# OPEnS-RTC-1_1.net
KiCad netlist of a schematic drawn in EAGLE
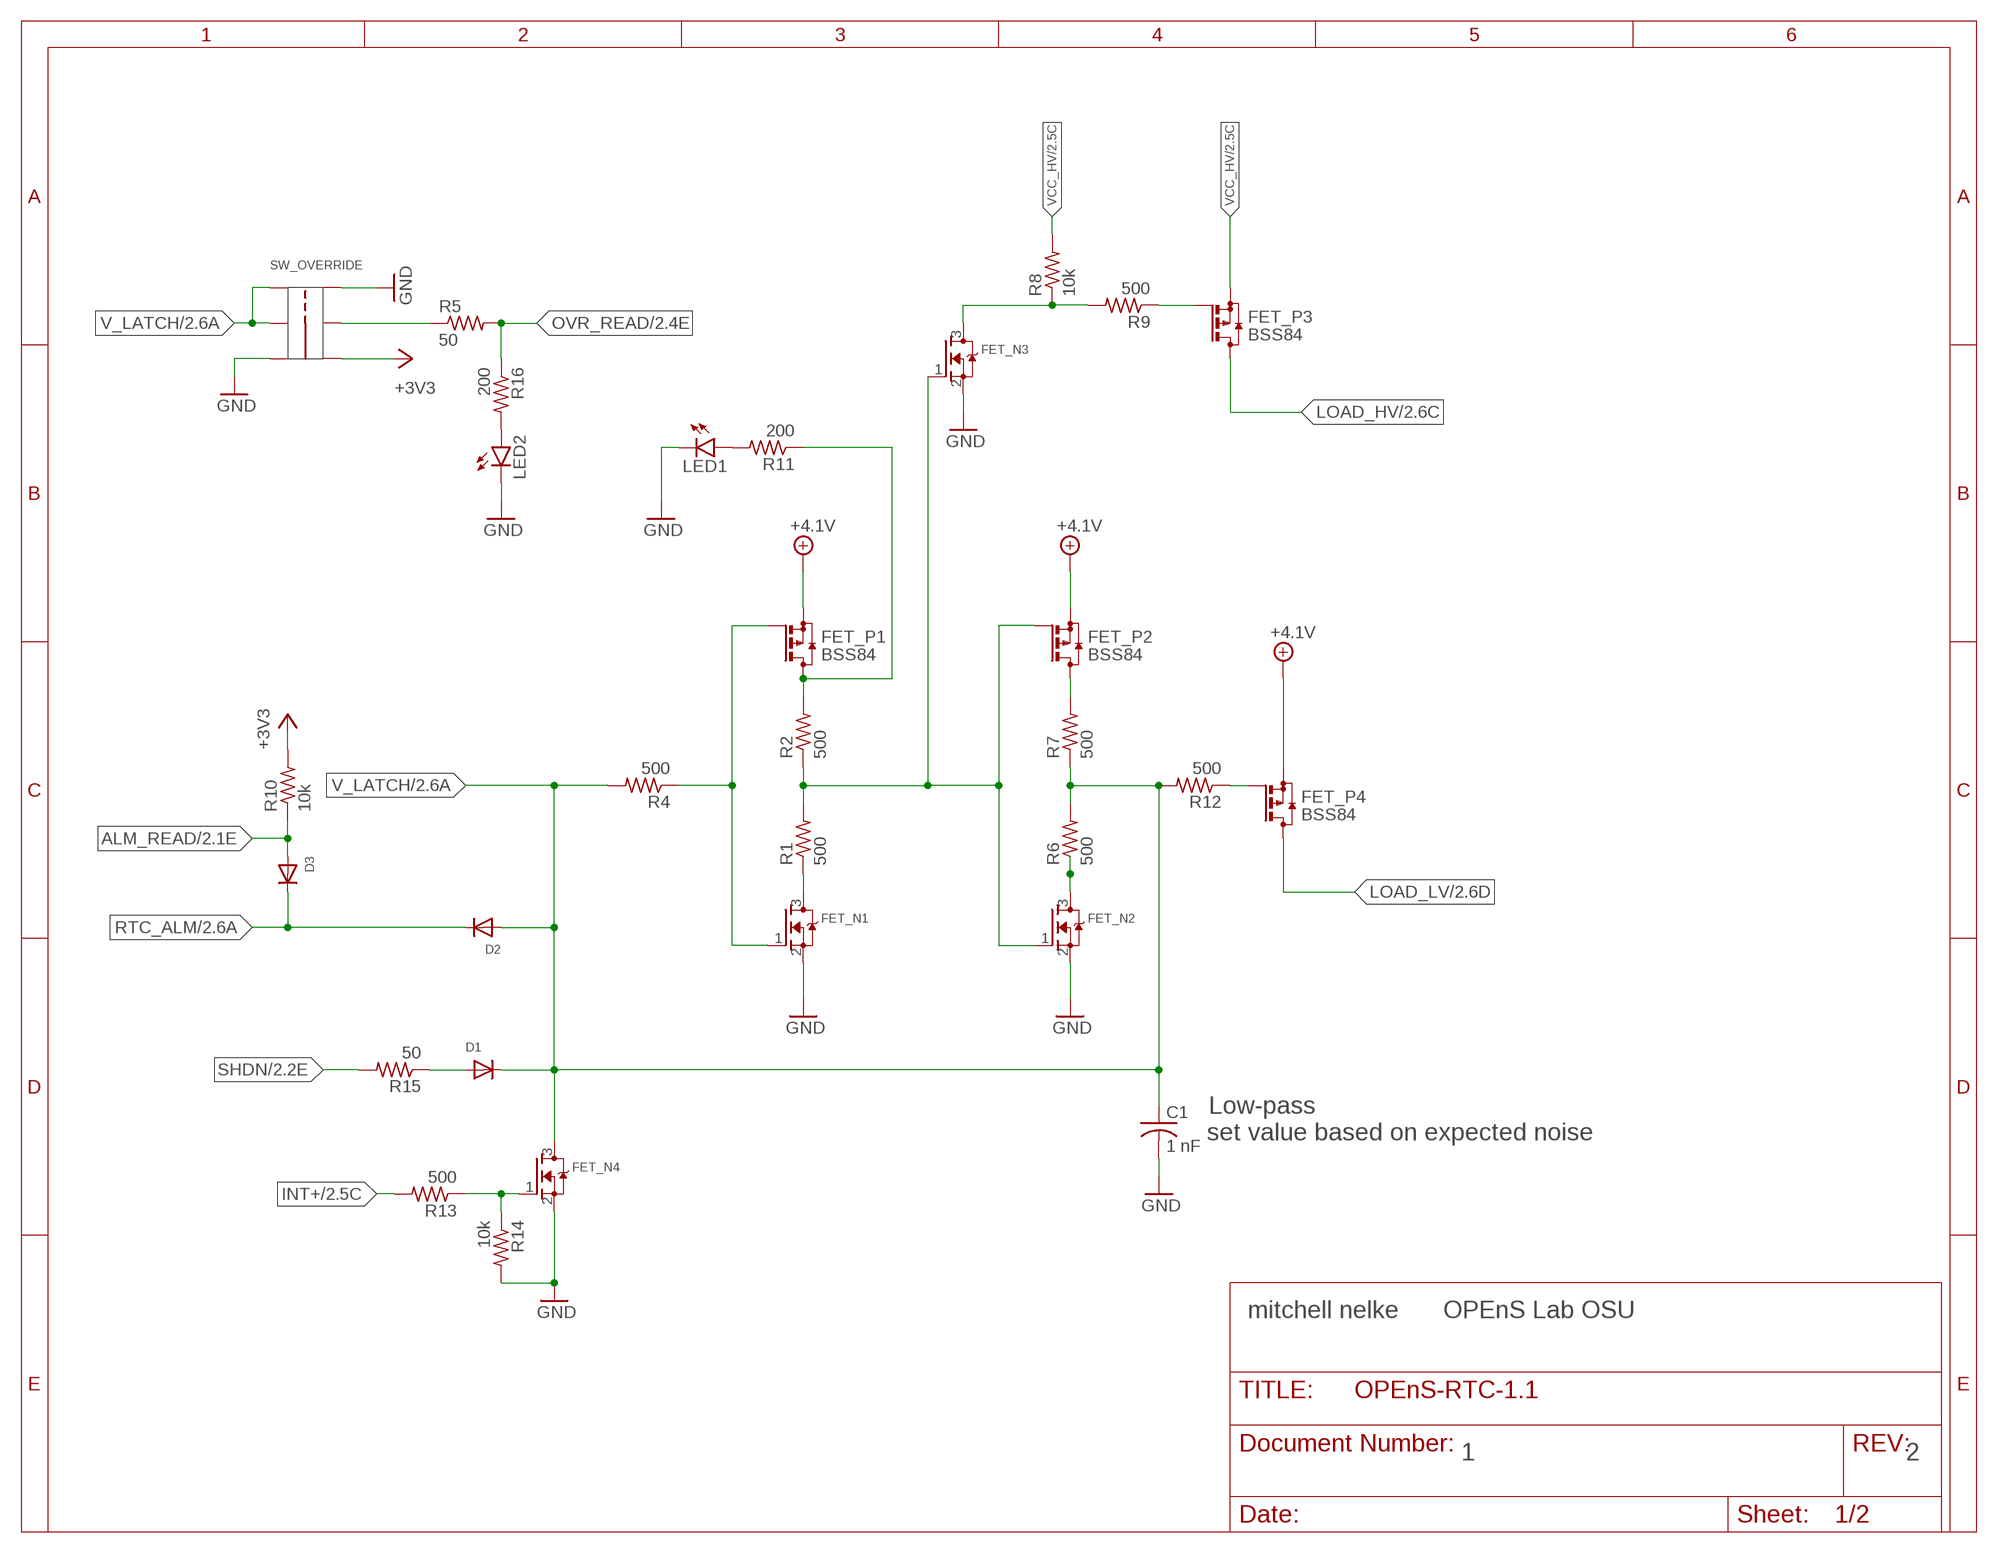
[diagram p0: schematic, sheet 1]
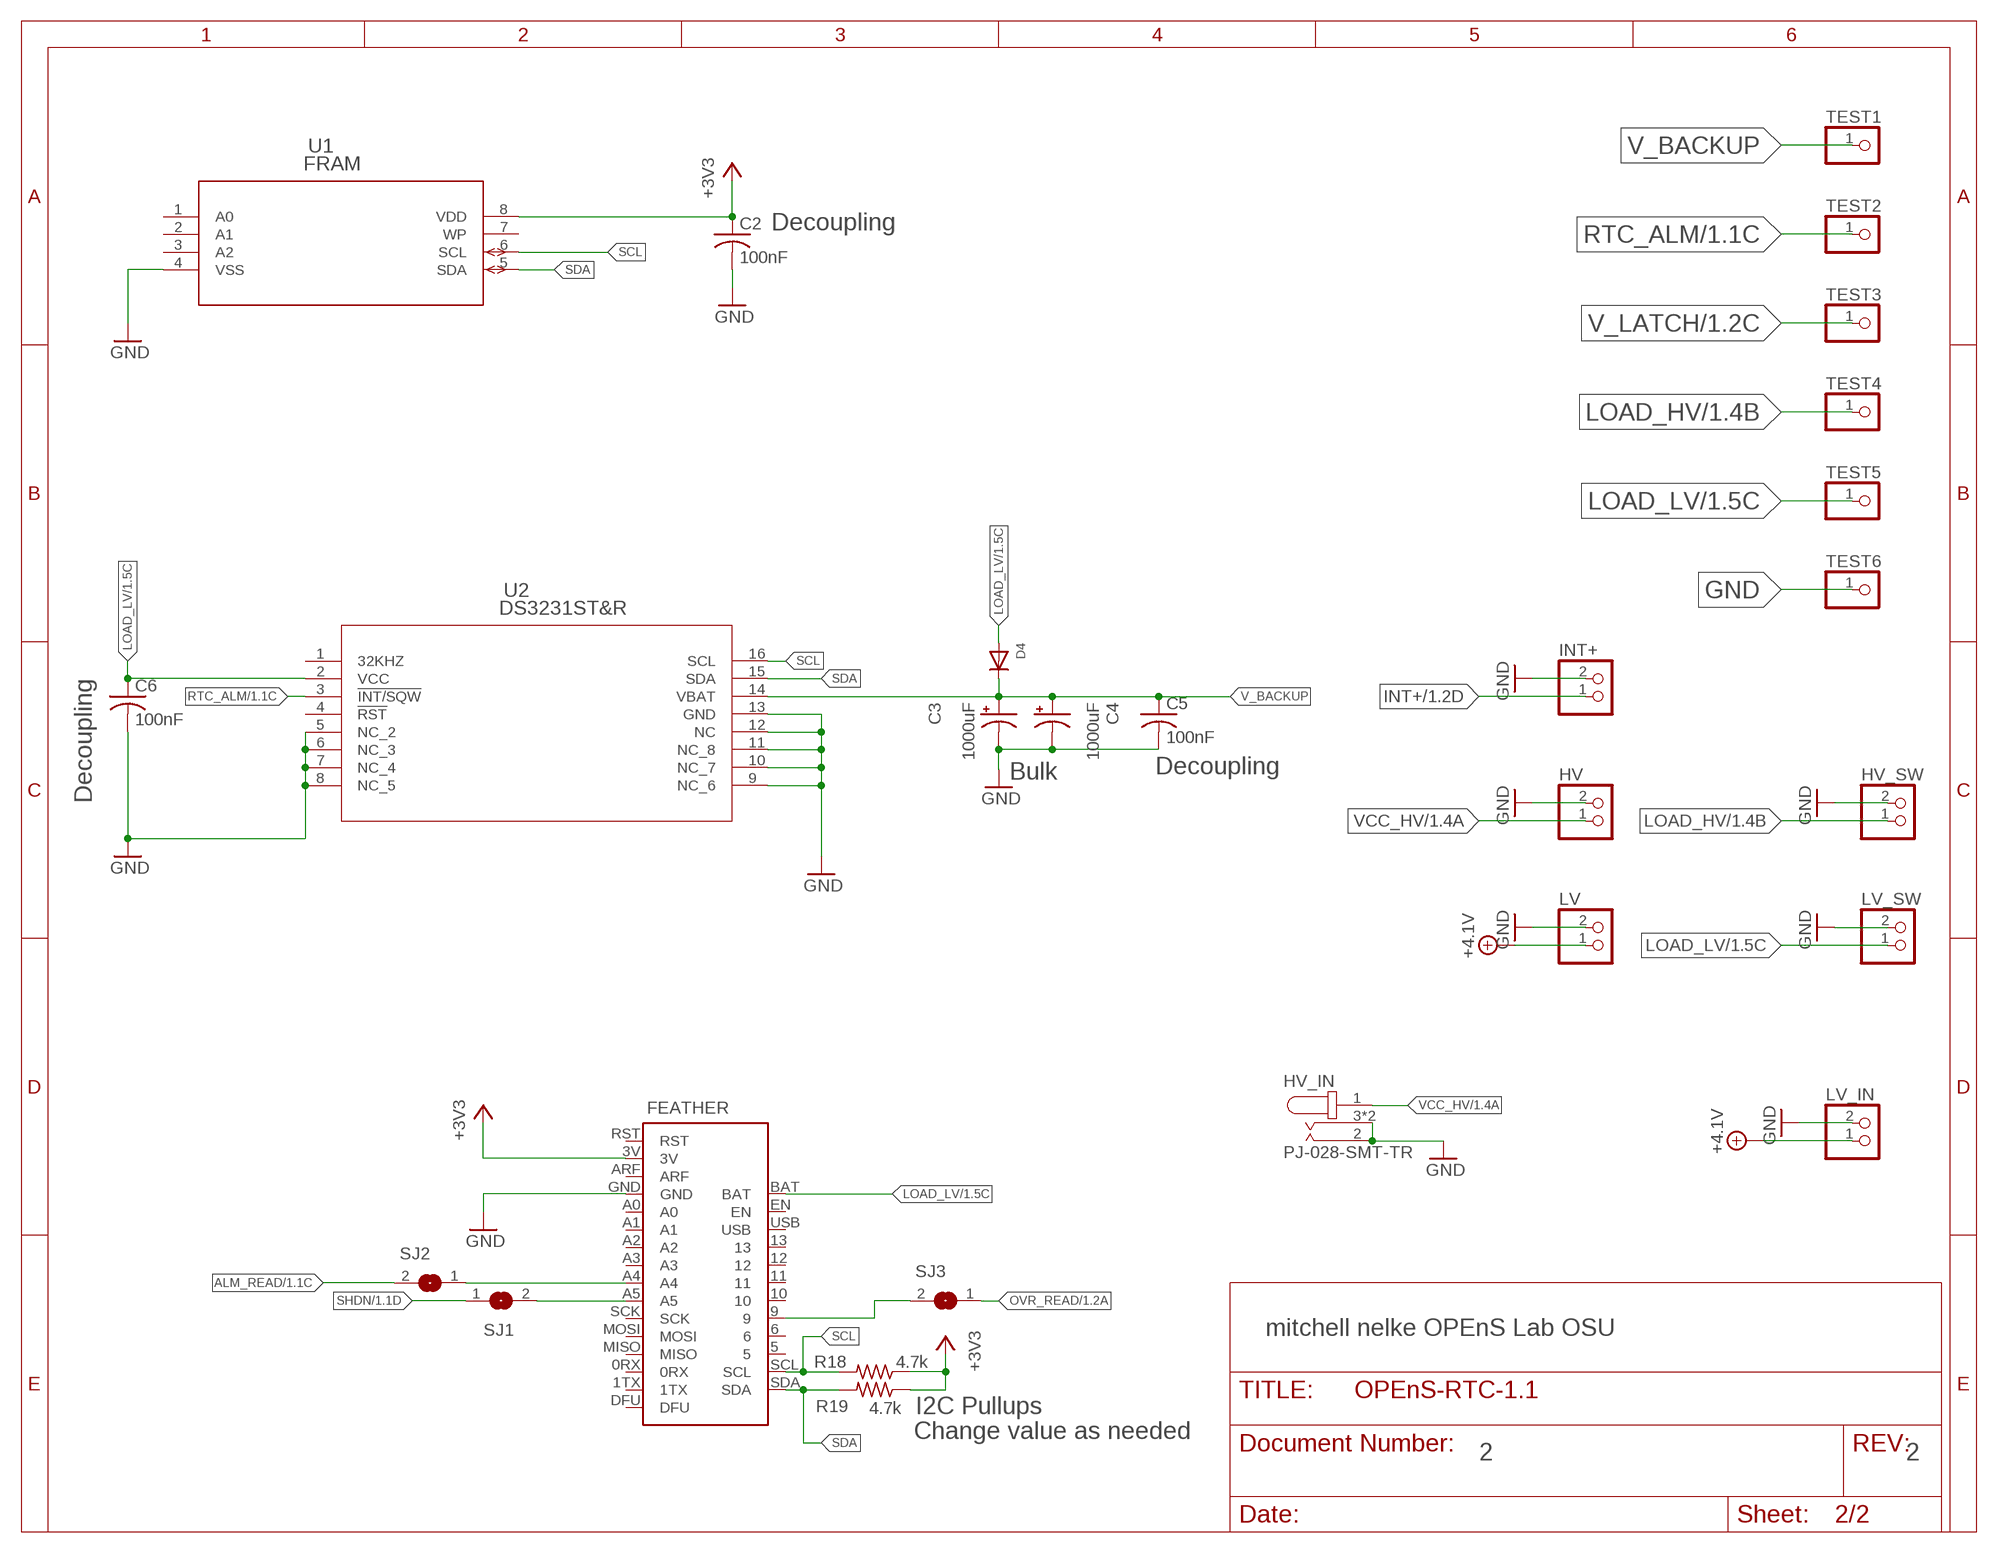
[diagram p1: schematic, sheet 2]

(export (version "E")
  (design (tool "Eeschema 10.0.6"))
  (components
    (comp (ref "C1")
      (value "1 nF")
      (footprint "eagle-import:C0805")
      (libsource (lib "eagle-import") (part "rcl_334_C-USC0805"))
    )
    (comp (ref "D1")
      (value "DIODESOD-123")
      (footprint "eagle-import:SOD-123")
      (libsource (lib "eagle-import") (part "DIODESOD-123"))
    )
    (comp (ref "D2")
      (value "DIODESOD-123")
      (footprint "eagle-import:SOD-123")
      (libsource (lib "eagle-import") (part "DIODESOD-123"))
    )
    (comp (ref "D3")
      (value "DIODESOD-123")
      (footprint "eagle-import:SOD-123")
      (libsource (lib "eagle-import") (part "DIODESOD-123"))
    )
    (comp (ref "FET_N1")
      (value "MOSFET-NREFLOW")
      (footprint "eagle-import:SOT23")
      (libsource (lib "eagle-import") (part "MOSFET-NREFLOW"))
    )
    (comp (ref "FET_N2")
      (value "MOSFET-NREFLOW")
      (footprint "eagle-import:SOT23")
      (libsource (lib "eagle-import") (part "MOSFET-NREFLOW"))
    )
    (comp (ref "FET_N3")
      (value "MOSFET-NREFLOW")
      (footprint "eagle-import:SOT23")
      (libsource (lib "eagle-import") (part "MOSFET-NREFLOW"))
    )
    (comp (ref "FET_N4")
      (value "MOSFET-NREFLOW")
      (footprint "eagle-import:SOT23")
      (libsource (lib "eagle-import") (part "MOSFET-NREFLOW"))
    )
    (comp (ref "FET_P1")
      (value "BSS84")
      (footprint "eagle-import:SOT23")
      (libsource (lib "eagle-import") (part "BSS84"))
    )
    (comp (ref "FET_P2")
      (value "BSS84")
      (footprint "eagle-import:SOT23")
      (libsource (lib "eagle-import") (part "BSS84"))
    )
    (comp (ref "FET_P3")
      (value "BSS84")
      (footprint "eagle-import:SOT23")
      (libsource (lib "eagle-import") (part "BSS84"))
    )
    (comp (ref "FET_P4")
      (value "BSS84")
      (footprint "eagle-import:SOT23")
      (libsource (lib "eagle-import") (part "BSS84"))
    )
    (comp (ref "LED1")
      (value "LEDSMT1206")
      (footprint "eagle-import:1206")
      (libsource (lib "eagle-import") (part "LEDSMT1206"))
    )
    (comp (ref "LED2")
      (value "LEDSMT1206")
      (footprint "eagle-import:1206")
      (libsource (lib "eagle-import") (part "LEDSMT1206"))
    )
    (comp (ref "R1")
      (value "500")
      (footprint "eagle-import:R0805")
      (libsource (lib "eagle-import") (part "rcl_334_R-US_R0805"))
    )
    (comp (ref "R2")
      (value "500")
      (footprint "eagle-import:R0805")
      (libsource (lib "eagle-import") (part "rcl_334_R-US_R0805"))
    )
    (comp (ref "R4")
      (value "500")
      (footprint "eagle-import:R0805")
      (libsource (lib "eagle-import") (part "rcl_334_R-US_R0805"))
    )
    (comp (ref "R5")
      (value "50")
      (footprint "eagle-import:R0805")
      (libsource (lib "eagle-import") (part "rcl_334_R-US_R0805"))
    )
    (comp (ref "R6")
      (value "500")
      (footprint "eagle-import:R0805")
      (libsource (lib "eagle-import") (part "rcl_334_R-US_R0805"))
    )
    (comp (ref "R7")
      (value "500")
      (footprint "eagle-import:R0805")
      (libsource (lib "eagle-import") (part "rcl_334_R-US_R0805"))
    )
    (comp (ref "R8")
      (value "10k")
      (footprint "eagle-import:R0805")
      (libsource (lib "eagle-import") (part "rcl_334_R-US_R0805"))
    )
    (comp (ref "R9")
      (value "500")
      (footprint "eagle-import:R0805")
      (libsource (lib "eagle-import") (part "rcl_334_R-US_R0805"))
    )
    (comp (ref "R10")
      (value "10k")
      (footprint "eagle-import:R0805")
      (libsource (lib "eagle-import") (part "rcl_334_R-US_R0805"))
    )
    (comp (ref "R11")
      (value "200")
      (footprint "eagle-import:R0805")
      (libsource (lib "eagle-import") (part "rcl_334_R-US_R0805"))
    )
    (comp (ref "R12")
      (value "500")
      (footprint "eagle-import:R0805")
      (libsource (lib "eagle-import") (part "rcl_334_R-US_R0805"))
    )
    (comp (ref "R13")
      (value "500")
      (footprint "eagle-import:R0805")
      (libsource (lib "eagle-import") (part "rcl_334_R-US_R0805"))
    )
    (comp (ref "R14")
      (value "10k")
      (footprint "eagle-import:R0805")
      (libsource (lib "eagle-import") (part "rcl_334_R-US_R0805"))
    )
    (comp (ref "R15")
      (value "50")
      (footprint "eagle-import:R0805")
      (libsource (lib "eagle-import") (part "rcl_334_R-US_R0805"))
    )
    (comp (ref "R16")
      (value "200")
      (footprint "eagle-import:R0805")
      (libsource (lib "eagle-import") (part "rcl_334_R-US_R0805"))
    )
    (comp (ref "SW_OVERRIDE")
      (value "JS202011JCQN")
      (footprint "eagle-import:VERTICAL_MNT_SMT-J")
      (libsource (lib "eagle-import") (part "JS202011JCQN"))
    )
    (comp (ref "C2")
      (value "100nF")
      (footprint "eagle-import:C0805")
      (libsource (lib "eagle-import") (part "C-USC0805"))
    )
    (comp (ref "C3")
      (value "1000uF")
      (footprint "eagle-import:E3,5-8")
      (libsource (lib "eagle-import") (part "CPOL-USE3.5-8"))
    )
    (comp (ref "C4")
      (value "1000uF")
      (footprint "eagle-import:E3,5-8")
      (libsource (lib "eagle-import") (part "CPOL-USE3.5-8"))
    )
    (comp (ref "C5")
      (value "100nF")
      (footprint "eagle-import:C0805")
      (libsource (lib "eagle-import") (part "C-USC0805"))
    )
    (comp (ref "C6")
      (value "100nF")
      (footprint "eagle-import:C0805")
      (libsource (lib "eagle-import") (part "C-USC0805"))
    )
    (comp (ref "D4")
      (value "DIODESOD-123")
      (footprint "eagle-import:SOD-123")
      (libsource (lib "eagle-import") (part "DIODESOD-123"))
    )
    (comp (ref "FEATHER")
      (value "BLUEFRUIT_M0")
      (footprint "eagle-import:BLUEFRUIT_MO")
      (libsource (lib "eagle-import") (part "BLUEFRUIT_M0"))
    )
    (comp (ref "HV")
      (value "JST_2PIN-SMT")
      (footprint "eagle-import:JST-PH-2-SMT")
      (libsource (lib "eagle-import") (part "JST_2PIN-SMT"))
    )
    (comp (ref "HV_IN")
      (value "PJ-028-SMT-TR")
      (footprint "eagle-import:CUI_PJ-028-SMT-TR")
      (fields (field (name "DIGI-KEY_PART_NUMBER") "CP-028PJCT-ND") (field (name "MF") "CUI Inc."))
      (libsource (lib "eagle-import") (part "PJ-028-SMT-TR"))
    )
    (comp (ref "HV_SW")
      (value "JST_2PIN-SMT")
      (footprint "eagle-import:JST-PH-2-SMT")
      (libsource (lib "eagle-import") (part "JST_2PIN-SMT"))
    )
    (comp (ref "INT+")
      (value "JST_2PIN-SMT")
      (footprint "eagle-import:JST-PH-2-SMT")
      (libsource (lib "eagle-import") (part "JST_2PIN-SMT"))
    )
    (comp (ref "LV")
      (value "JST_2PIN-SMT")
      (footprint "eagle-import:JST-PH-2-SMT")
      (libsource (lib "eagle-import") (part "JST_2PIN-SMT"))
    )
    (comp (ref "LV_IN")
      (value "JST_2PIN-SMT")
      (footprint "eagle-import:JST-PH-2-SMT")
      (libsource (lib "eagle-import") (part "JST_2PIN-SMT"))
    )
    (comp (ref "LV_SW")
      (value "JST_2PIN-SMT")
      (footprint "eagle-import:JST-PH-2-SMT")
      (libsource (lib "eagle-import") (part "JST_2PIN-SMT"))
    )
    (comp (ref "R18")
      (value "4.7k")
      (footprint "eagle-import:M0805")
      (libsource (lib "eagle-import") (part "R-US_M0805"))
    )
    (comp (ref "R19")
      (value "4.7k")
      (footprint "eagle-import:M0805")
      (libsource (lib "eagle-import") (part "R-US_M0805"))
    )
    (comp (ref "SJ1") (value "SJ") (footprint "eagle-import:SJ") (libsource (lib "eagle-import") (part "SJ")))
    (comp (ref "SJ2") (value "SJ") (footprint "eagle-import:SJ") (libsource (lib "eagle-import") (part "SJ")))
    (comp (ref "SJ3") (value "SJ") (footprint "eagle-import:SJ") (libsource (lib "eagle-import") (part "SJ")))
    (comp (ref "TEST1")
      (value "PINHD-1X1")
      (footprint "eagle-import:1X01")
      (libsource (lib "eagle-import") (part "PINHD-1X1"))
    )
    (comp (ref "TEST2")
      (value "PINHD-1X1")
      (footprint "eagle-import:1X01")
      (libsource (lib "eagle-import") (part "PINHD-1X1"))
    )
    (comp (ref "TEST3")
      (value "PINHD-1X1")
      (footprint "eagle-import:1X01")
      (libsource (lib "eagle-import") (part "PINHD-1X1"))
    )
    (comp (ref "TEST4")
      (value "PINHD-1X1")
      (footprint "eagle-import:1X01")
      (libsource (lib "eagle-import") (part "PINHD-1X1"))
    )
    (comp (ref "TEST5")
      (value "PINHD-1X1")
      (footprint "eagle-import:1X01")
      (libsource (lib "eagle-import") (part "PINHD-1X1"))
    )
    (comp (ref "TEST6")
      (value "PINHD-1X1")
      (footprint "eagle-import:1X01")
      (libsource (lib "eagle-import") (part "PINHD-1X1"))
    )
    (comp (ref "U1")
      (value "FRAM")
      (footprint "eagle-import:FPT-8P-M02")
      (fields (field (name "MANUFACTURER_PART_NUMBER") "Inc."))
      (libsource (lib "eagle-import") (part "FRAM"))
    )
    (comp (ref "U2")
      (value "DS3231ST&R")
      (footprint "eagle-import:21-0042B_16")
      (fields (field (name "MANUFACTURER_PART_NUMBER") "DS3231S#T&R"))
      (libsource (lib "eagle-import") (part "DS3231ST&R"))
    )
  )
  (nets
    (net (code "1") (name "+3V3") (class "Default")
      (node (ref "C2") (pin "1") (pinfunction "1_1") (pintype "passive"))
      (node (ref "FEATHER") (pin "3V") (pinfunction "3V_3V") (pintype "bidirectional"))
      (node (ref "R10") (pin "2") (pinfunction "2_2") (pintype "passive"))
      (node (ref "R18") (pin "1") (pinfunction "1_1") (pintype "passive"))
      (node (ref "R19") (pin "1") (pinfunction "1_1") (pintype "passive"))
      (node (ref "SW_OVERRIDE") (pin "A_") (pinfunction "A__A_") (pintype "bidirectional"))
      (node (ref "U1") (pin "8") (pinfunction "VDD_8") (pintype "power_in"))
    )
    (net (code "2") (name "+4.1V") (class "Default")
      (node (ref "FET_P1") (pin "2") (pinfunction "S_2") (pintype "passive"))
      (node (ref "FET_P2") (pin "2") (pinfunction "S_2") (pintype "passive"))
      (node (ref "FET_P4") (pin "2") (pinfunction "S_2") (pintype "passive"))
      (node (ref "LV") (pin "1") (pinfunction "2_1") (pintype "passive"))
      (node (ref "LV_IN") (pin "1") (pinfunction "2_1") (pintype "passive"))
    )
    (net (code "3") (name "ALM_READ") (class "Default")
      (node (ref "D3") (pin "A") (pinfunction "A_A") (pintype "passive"))
      (node (ref "R10") (pin "1") (pinfunction "1_1") (pintype "passive"))
      (node (ref "SJ2") (pin "2") (pinfunction "2_2") (pintype "passive"))
    )
    (net (code "4") (name "GND") (class "Default")
      (node (ref "C1") (pin "2") (pinfunction "2_2") (pintype "passive"))
      (node (ref "C2") (pin "2") (pinfunction "2_2") (pintype "passive"))
      (node (ref "C3") (pin "-") (pinfunction "-_-") (pintype "passive"))
      (node (ref "C4") (pin "-") (pinfunction "-_-") (pintype "passive"))
      (node (ref "C5") (pin "2") (pinfunction "2_2") (pintype "passive"))
      (node (ref "C6") (pin "2") (pinfunction "2_2") (pintype "passive"))
      (node (ref "FEATHER") (pin "GND") (pinfunction "GND_GND") (pintype "bidirectional"))
      (node (ref "FET_N1") (pin "2") (pinfunction "S_2") (pintype "bidirectional"))
      (node (ref "FET_N2") (pin "2") (pinfunction "S_2") (pintype "bidirectional"))
      (node (ref "FET_N3") (pin "2") (pinfunction "S_2") (pintype "bidirectional"))
      (node (ref "FET_N4") (pin "2") (pinfunction "S_2") (pintype "bidirectional"))
      (node (ref "HV") (pin "2") (pinfunction "1_2") (pintype "passive"))
      (node (ref "HV_IN") (pin "2") (pinfunction "2_2") (pintype "passive"))
      (node (ref "HV_IN") (pin "3") (pinfunction "3_3") (pintype "passive"))
      (node (ref "HV_IN") (pin "3.1") (pinfunction "3_3.1") (pintype "passive"))
      (node (ref "HV_SW") (pin "2") (pinfunction "1_2") (pintype "passive"))
      (node (ref "INT+") (pin "2") (pinfunction "1_2") (pintype "passive"))
      (node (ref "LED1") (pin "C") (pinfunction "C_C") (pintype "passive"))
      (node (ref "LED2") (pin "C") (pinfunction "C_C") (pintype "passive"))
      (node (ref "LV") (pin "2") (pinfunction "1_2") (pintype "passive"))
      (node (ref "LV_IN") (pin "2") (pinfunction "1_2") (pintype "passive"))
      (node (ref "LV_SW") (pin "2") (pinfunction "1_2") (pintype "passive"))
      (node (ref "R14") (pin "2") (pinfunction "2_2") (pintype "passive"))
      (node (ref "SW_OVERRIDE") (pin "A") (pinfunction "A_A") (pintype "bidirectional"))
      (node (ref "SW_OVERRIDE") (pin "B_") (pinfunction "B__B_") (pintype "bidirectional"))
      (node (ref "TEST6") (pin "1") (pinfunction "1_1") (pintype "passive"))
      (node (ref "U1") (pin "4") (pinfunction "VSS_4") (pintype "power_in"))
      (node (ref "U2") (pin "10") (pinfunction "NC_7_10") (pintype "passive"))
      (node (ref "U2") (pin "11") (pinfunction "NC_8_11") (pintype "passive"))
      (node (ref "U2") (pin "12") (pinfunction "NC_12") (pintype "passive"))
      (node (ref "U2") (pin "13") (pinfunction "GND_13") (pintype "power_in"))
      (node (ref "U2") (pin "5") (pinfunction "NC_2_5") (pintype "passive"))
      (node (ref "U2") (pin "6") (pinfunction "NC_3_6") (pintype "passive"))
      (node (ref "U2") (pin "7") (pinfunction "NC_4_7") (pintype "passive"))
      (node (ref "U2") (pin "8") (pinfunction "NC_5_8") (pintype "passive"))
      (node (ref "U2") (pin "9") (pinfunction "NC_6_9") (pintype "passive"))
    )
    (net (code "5") (name "INT+") (class "Default")
      (node (ref "INT+") (pin "1") (pinfunction "2_1") (pintype "passive"))
      (node (ref "R13") (pin "2") (pinfunction "2_2") (pintype "passive"))
    )
    (net (code "6") (name "LOAD_HV") (class "Default")
      (node (ref "FET_P3") (pin "3") (pinfunction "D_3") (pintype "passive"))
      (node (ref "HV_SW") (pin "1") (pinfunction "2_1") (pintype "passive"))
      (node (ref "TEST4") (pin "1") (pinfunction "1_1") (pintype "passive"))
    )
    (net (code "7") (name "LOAD_LV") (class "Default")
      (node (ref "C6") (pin "1") (pinfunction "1_1") (pintype "passive"))
      (node (ref "D4") (pin "A") (pinfunction "A_A") (pintype "passive"))
      (node (ref "FEATHER") (pin "BAT") (pinfunction "BAT_BAT") (pintype "bidirectional"))
      (node (ref "FET_P4") (pin "3") (pinfunction "D_3") (pintype "passive"))
      (node (ref "LV_SW") (pin "1") (pinfunction "2_1") (pintype "passive"))
      (node (ref "TEST5") (pin "1") (pinfunction "1_1") (pintype "passive"))
      (node (ref "U2") (pin "2") (pinfunction "VCC_2") (pintype "power_in"))
    )
    (net (code "8") (name "Net-(D1-PadA)") (class "Default")
      (node (ref "D1") (pin "A") (pinfunction "A_A") (pintype "passive"))
      (node (ref "R15") (pin "1") (pinfunction "1_1") (pintype "passive"))
    )
    (net (code "9") (name "Net-(FEATHER-Pad9)") (class "Default")
      (node (ref "FEATHER") (pin "9") (pinfunction "9_9") (pintype "bidirectional"))
      (node (ref "SJ3") (pin "2") (pinfunction "2_2") (pintype "passive"))
    )
    (net (code "10") (name "Net-(FEATHER-PadA4)") (class "Default")
      (node (ref "FEATHER") (pin "A4") (pinfunction "A4_A4") (pintype "bidirectional"))
      (node (ref "SJ2") (pin "1") (pinfunction "1_1") (pintype "passive"))
    )
    (net (code "11") (name "Net-(FEATHER-PadA5)") (class "Default")
      (node (ref "FEATHER") (pin "A5") (pinfunction "A5_A5") (pintype "bidirectional"))
      (node (ref "SJ1") (pin "2") (pinfunction "2_2") (pintype "passive"))
    )
    (net (code "12") (name "Net-(FET_N1-D)") (class "Default")
      (node (ref "FET_N1") (pin "3") (pinfunction "D_3") (pintype "bidirectional"))
      (node (ref "R1") (pin "1") (pinfunction "1_1") (pintype "passive"))
    )
    (net (code "13") (name "Net-(FET_N1-G)") (class "Default")
      (node (ref "FET_N1") (pin "1") (pinfunction "G_1") (pintype "bidirectional"))
      (node (ref "FET_P1") (pin "1") (pinfunction "G_1") (pintype "passive"))
      (node (ref "R4") (pin "1") (pinfunction "1_1") (pintype "passive"))
    )
    (net (code "14") (name "Net-(FET_N2-D)") (class "Default")
      (node (ref "FET_N2") (pin "3") (pinfunction "D_3") (pintype "bidirectional"))
      (node (ref "R6") (pin "1") (pinfunction "1_1") (pintype "passive"))
    )
    (net (code "15") (name "Net-(FET_N2-G)") (class "Default")
      (node (ref "FET_N2") (pin "1") (pinfunction "G_1") (pintype "bidirectional"))
      (node (ref "FET_N3") (pin "1") (pinfunction "G_1") (pintype "bidirectional"))
      (node (ref "FET_P2") (pin "1") (pinfunction "G_1") (pintype "passive"))
      (node (ref "R1") (pin "2") (pinfunction "2_2") (pintype "passive"))
      (node (ref "R2") (pin "1") (pinfunction "1_1") (pintype "passive"))
    )
    (net (code "16") (name "Net-(FET_N3-D)") (class "Default")
      (node (ref "FET_N3") (pin "3") (pinfunction "D_3") (pintype "bidirectional"))
      (node (ref "R8") (pin "1") (pinfunction "1_1") (pintype "passive"))
      (node (ref "R9") (pin "2") (pinfunction "2_2") (pintype "passive"))
    )
    (net (code "17") (name "Net-(FET_N4-G)") (class "Default")
      (node (ref "FET_N4") (pin "1") (pinfunction "G_1") (pintype "bidirectional"))
      (node (ref "R13") (pin "1") (pinfunction "1_1") (pintype "passive"))
      (node (ref "R14") (pin "1") (pinfunction "1_1") (pintype "passive"))
    )
    (net (code "18") (name "Net-(FET_P1-D)") (class "Default")
      (node (ref "FET_P1") (pin "3") (pinfunction "D_3") (pintype "passive"))
      (node (ref "R11") (pin "1") (pinfunction "1_1") (pintype "passive"))
      (node (ref "R2") (pin "2") (pinfunction "2_2") (pintype "passive"))
    )
    (net (code "19") (name "Net-(FET_P2-D)") (class "Default")
      (node (ref "FET_P2") (pin "3") (pinfunction "D_3") (pintype "passive"))
      (node (ref "R7") (pin "2") (pinfunction "2_2") (pintype "passive"))
    )
    (net (code "20") (name "Net-(FET_P3-G)") (class "Default")
      (node (ref "FET_P3") (pin "1") (pinfunction "G_1") (pintype "passive"))
      (node (ref "R9") (pin "1") (pinfunction "1_1") (pintype "passive"))
    )
    (net (code "21") (name "Net-(FET_P4-G)") (class "Default")
      (node (ref "FET_P4") (pin "1") (pinfunction "G_1") (pintype "passive"))
      (node (ref "R12") (pin "1") (pinfunction "1_1") (pintype "passive"))
    )
    (net (code "22") (name "Net-(LED1-PadA)") (class "Default")
      (node (ref "LED1") (pin "A") (pinfunction "A_A") (pintype "passive"))
      (node (ref "R11") (pin "2") (pinfunction "2_2") (pintype "passive"))
    )
    (net (code "23") (name "Net-(LED2-PadA)") (class "Default")
      (node (ref "LED2") (pin "A") (pinfunction "A_A") (pintype "passive"))
      (node (ref "R16") (pin "2") (pinfunction "2_2") (pintype "passive"))
    )
    (net (code "24") (name "Net-(R5-Pad1)") (class "Default")
      (node (ref "R5") (pin "1") (pinfunction "1_1") (pintype "passive"))
      (node (ref "SW_OVERRIDE") (pin "COM_") (pinfunction "COM__COM_") (pintype "bidirectional"))
    )
    (net (code "25") (name "OVR_READ") (class "Default")
      (node (ref "R16") (pin "1") (pinfunction "1_1") (pintype "passive"))
      (node (ref "R5") (pin "2") (pinfunction "2_2") (pintype "passive"))
      (node (ref "SJ3") (pin "1") (pinfunction "1_1") (pintype "passive"))
    )
    (net (code "26") (name "RTC_ALM") (class "Default")
      (node (ref "D2") (pin "C") (pinfunction "C_C") (pintype "passive"))
      (node (ref "D3") (pin "C") (pinfunction "C_C") (pintype "passive"))
      (node (ref "TEST2") (pin "1") (pinfunction "1_1") (pintype "passive"))
      (node (ref "U2") (pin "3") (pinfunction "~{INT/SQW}_3") (pintype "passive"))
    )
    (net (code "27") (name "SCL") (class "Default")
      (node (ref "FEATHER") (pin "SCL") (pinfunction "SCL_SCL") (pintype "bidirectional"))
      (node (ref "R18") (pin "2") (pinfunction "2_2") (pintype "passive"))
      (node (ref "U1") (pin "6") (pinfunction "SCL_6") (pintype "bidirectional"))
      (node (ref "U2") (pin "16") (pinfunction "SCL_16") (pintype "passive"))
    )
    (net (code "28") (name "SDA") (class "Default")
      (node (ref "FEATHER") (pin "SDA") (pinfunction "SDA_SDA") (pintype "bidirectional"))
      (node (ref "R19") (pin "2") (pinfunction "2_2") (pintype "passive"))
      (node (ref "U1") (pin "5") (pinfunction "SDA_5") (pintype "bidirectional"))
      (node (ref "U2") (pin "15") (pinfunction "SDA_15") (pintype "passive"))
    )
    (net (code "29") (name "SHDN") (class "Default")
      (node (ref "R15") (pin "2") (pinfunction "2_2") (pintype "passive"))
      (node (ref "SJ1") (pin "1") (pinfunction "1_1") (pintype "passive"))
    )
    (net (code "30") (name "VCC_HV") (class "Default")
      (node (ref "FET_P3") (pin "2") (pinfunction "S_2") (pintype "passive"))
      (node (ref "HV") (pin "1") (pinfunction "2_1") (pintype "passive"))
      (node (ref "HV_IN") (pin "1") (pinfunction "1_1") (pintype "passive"))
      (node (ref "R8") (pin "2") (pinfunction "2_2") (pintype "passive"))
    )
    (net (code "31") (name "V_BACKUP") (class "Default")
      (node (ref "C3") (pin "+") (pinfunction "+_+") (pintype "passive"))
      (node (ref "C4") (pin "+") (pinfunction "+_+") (pintype "passive"))
      (node (ref "C5") (pin "1") (pinfunction "1_1") (pintype "passive"))
      (node (ref "D4") (pin "C") (pinfunction "C_C") (pintype "passive"))
      (node (ref "TEST1") (pin "1") (pinfunction "1_1") (pintype "passive"))
      (node (ref "U2") (pin "14") (pinfunction "VBAT_14") (pintype "power_in"))
    )
    (net (code "32") (name "V_LATCH") (class "Default")
      (node (ref "C1") (pin "1") (pinfunction "1_1") (pintype "passive"))
      (node (ref "D1") (pin "C") (pinfunction "C_C") (pintype "passive"))
      (node (ref "D2") (pin "A") (pinfunction "A_A") (pintype "passive"))
      (node (ref "FET_N4") (pin "3") (pinfunction "D_3") (pintype "bidirectional"))
      (node (ref "R12") (pin "2") (pinfunction "2_2") (pintype "passive"))
      (node (ref "R4") (pin "2") (pinfunction "2_2") (pintype "passive"))
      (node (ref "R6") (pin "2") (pinfunction "2_2") (pintype "passive"))
      (node (ref "R7") (pin "1") (pinfunction "1_1") (pintype "passive"))
      (node (ref "SW_OVERRIDE") (pin "B") (pinfunction "B_B") (pintype "bidirectional"))
      (node (ref "SW_OVERRIDE") (pin "COM") (pinfunction "COM_COM") (pintype "bidirectional"))
      (node (ref "TEST3") (pin "1") (pinfunction "1_1") (pintype "passive"))
    )
    (net (code "33") (name "unconnected-(FEATHER-Pad0RX)") (class "Default")
      (node (ref "FEATHER") (pin "0RX") (pinfunction "0RX_0RX") (pintype "bidirectional"))
    )
    (net (code "34") (name "unconnected-(FEATHER-Pad1TX)") (class "Default")
      (node (ref "FEATHER") (pin "1TX") (pinfunction "1TX_1TX") (pintype "bidirectional"))
    )
    (net (code "35") (name "unconnected-(FEATHER-Pad5)") (class "Default")
      (node (ref "FEATHER") (pin "5") (pinfunction "5_5") (pintype "bidirectional"))
    )
    (net (code "36") (name "unconnected-(FEATHER-Pad6)") (class "Default")
      (node (ref "FEATHER") (pin "6") (pinfunction "6_6") (pintype "bidirectional"))
    )
    (net (code "37") (name "unconnected-(FEATHER-Pad10)") (class "Default")
      (node (ref "FEATHER") (pin "10") (pinfunction "10_10") (pintype "bidirectional"))
    )
    (net (code "38") (name "unconnected-(FEATHER-Pad11)") (class "Default")
      (node (ref "FEATHER") (pin "11") (pinfunction "11_11") (pintype "bidirectional"))
    )
    (net (code "39") (name "unconnected-(FEATHER-Pad12)") (class "Default")
      (node (ref "FEATHER") (pin "12") (pinfunction "12_12") (pintype "bidirectional"))
    )
    (net (code "40") (name "unconnected-(FEATHER-Pad13)") (class "Default")
      (node (ref "FEATHER") (pin "13") (pinfunction "13_13") (pintype "bidirectional"))
    )
    (net (code "41") (name "unconnected-(FEATHER-PadA0)") (class "Default")
      (node (ref "FEATHER") (pin "A0") (pinfunction "A0_A0") (pintype "bidirectional"))
    )
    (net (code "42") (name "unconnected-(FEATHER-PadA1)") (class "Default")
      (node (ref "FEATHER") (pin "A1") (pinfunction "A1_A1") (pintype "bidirectional"))
    )
    (net (code "43") (name "unconnected-(FEATHER-PadA2)") (class "Default")
      (node (ref "FEATHER") (pin "A2") (pinfunction "A2_A2") (pintype "bidirectional"))
    )
    (net (code "44") (name "unconnected-(FEATHER-PadA3)") (class "Default")
      (node (ref "FEATHER") (pin "A3") (pinfunction "A3_A3") (pintype "bidirectional"))
    )
    (net (code "45") (name "unconnected-(FEATHER-PadARF)") (class "Default")
      (node (ref "FEATHER") (pin "ARF") (pinfunction "ARF_ARF") (pintype "bidirectional"))
    )
    (net (code "46") (name "unconnected-(FEATHER-PadDFU)") (class "Default")
      (node (ref "FEATHER") (pin "DFU") (pinfunction "DFU_DFU") (pintype "bidirectional"))
    )
    (net (code "47") (name "unconnected-(FEATHER-PadEN)") (class "Default")
      (node (ref "FEATHER") (pin "EN") (pinfunction "EN_EN") (pintype "bidirectional"))
    )
    (net (code "48") (name "unconnected-(FEATHER-PadMISO)") (class "Default")
      (node (ref "FEATHER") (pin "MISO") (pinfunction "MISO_MISO") (pintype "bidirectional"))
    )
    (net (code "49") (name "unconnected-(FEATHER-PadMOSI)") (class "Default")
      (node (ref "FEATHER") (pin "MOSI") (pinfunction "MOSI_MOSI") (pintype "bidirectional"))
    )
    (net (code "50") (name "unconnected-(FEATHER-PadRST)") (class "Default")
      (node (ref "FEATHER") (pin "RST") (pinfunction "RST_RST") (pintype "bidirectional"))
    )
    (net (code "51") (name "unconnected-(FEATHER-PadSCK)") (class "Default")
      (node (ref "FEATHER") (pin "SCK") (pinfunction "SCK_SCK") (pintype "bidirectional"))
    )
    (net (code "52") (name "unconnected-(FEATHER-PadUSB)") (class "Default")
      (node (ref "FEATHER") (pin "USB") (pinfunction "USB_USB") (pintype "bidirectional"))
    )
    (net (code "53") (name "unconnected-(U1-A0-Pad1)") (class "Default")
      (node (ref "U1") (pin "1") (pinfunction "A0_1") (pintype "passive"))
    )
    (net (code "54") (name "unconnected-(U1-A1-Pad2)") (class "Default")
      (node (ref "U1") (pin "2") (pinfunction "A1_2") (pintype "passive"))
    )
    (net (code "55") (name "unconnected-(U1-A2-Pad3)") (class "Default")
      (node (ref "U1") (pin "3") (pinfunction "A2_3") (pintype "passive"))
    )
    (net (code "56") (name "unconnected-(U1-WP-Pad7)") (class "Default")
      (node (ref "U1") (pin "7") (pinfunction "WP_7") (pintype "passive"))
    )
    (net (code "57") (name "unconnected-(U2-32KHZ-Pad1)") (class "Default")
      (node (ref "U2") (pin "1") (pinfunction "32KHZ_1") (pintype "passive"))
    )
    (net (code "58") (name "unconnected-(U2-~{RST}-Pad4)") (class "Default")
      (node (ref "U2") (pin "4") (pinfunction "~{RST}_4") (pintype "passive"))
    )
  )
)
